# 03_MotorDriver.net
KiCad netlist of a schematic drawn in Altium Designer
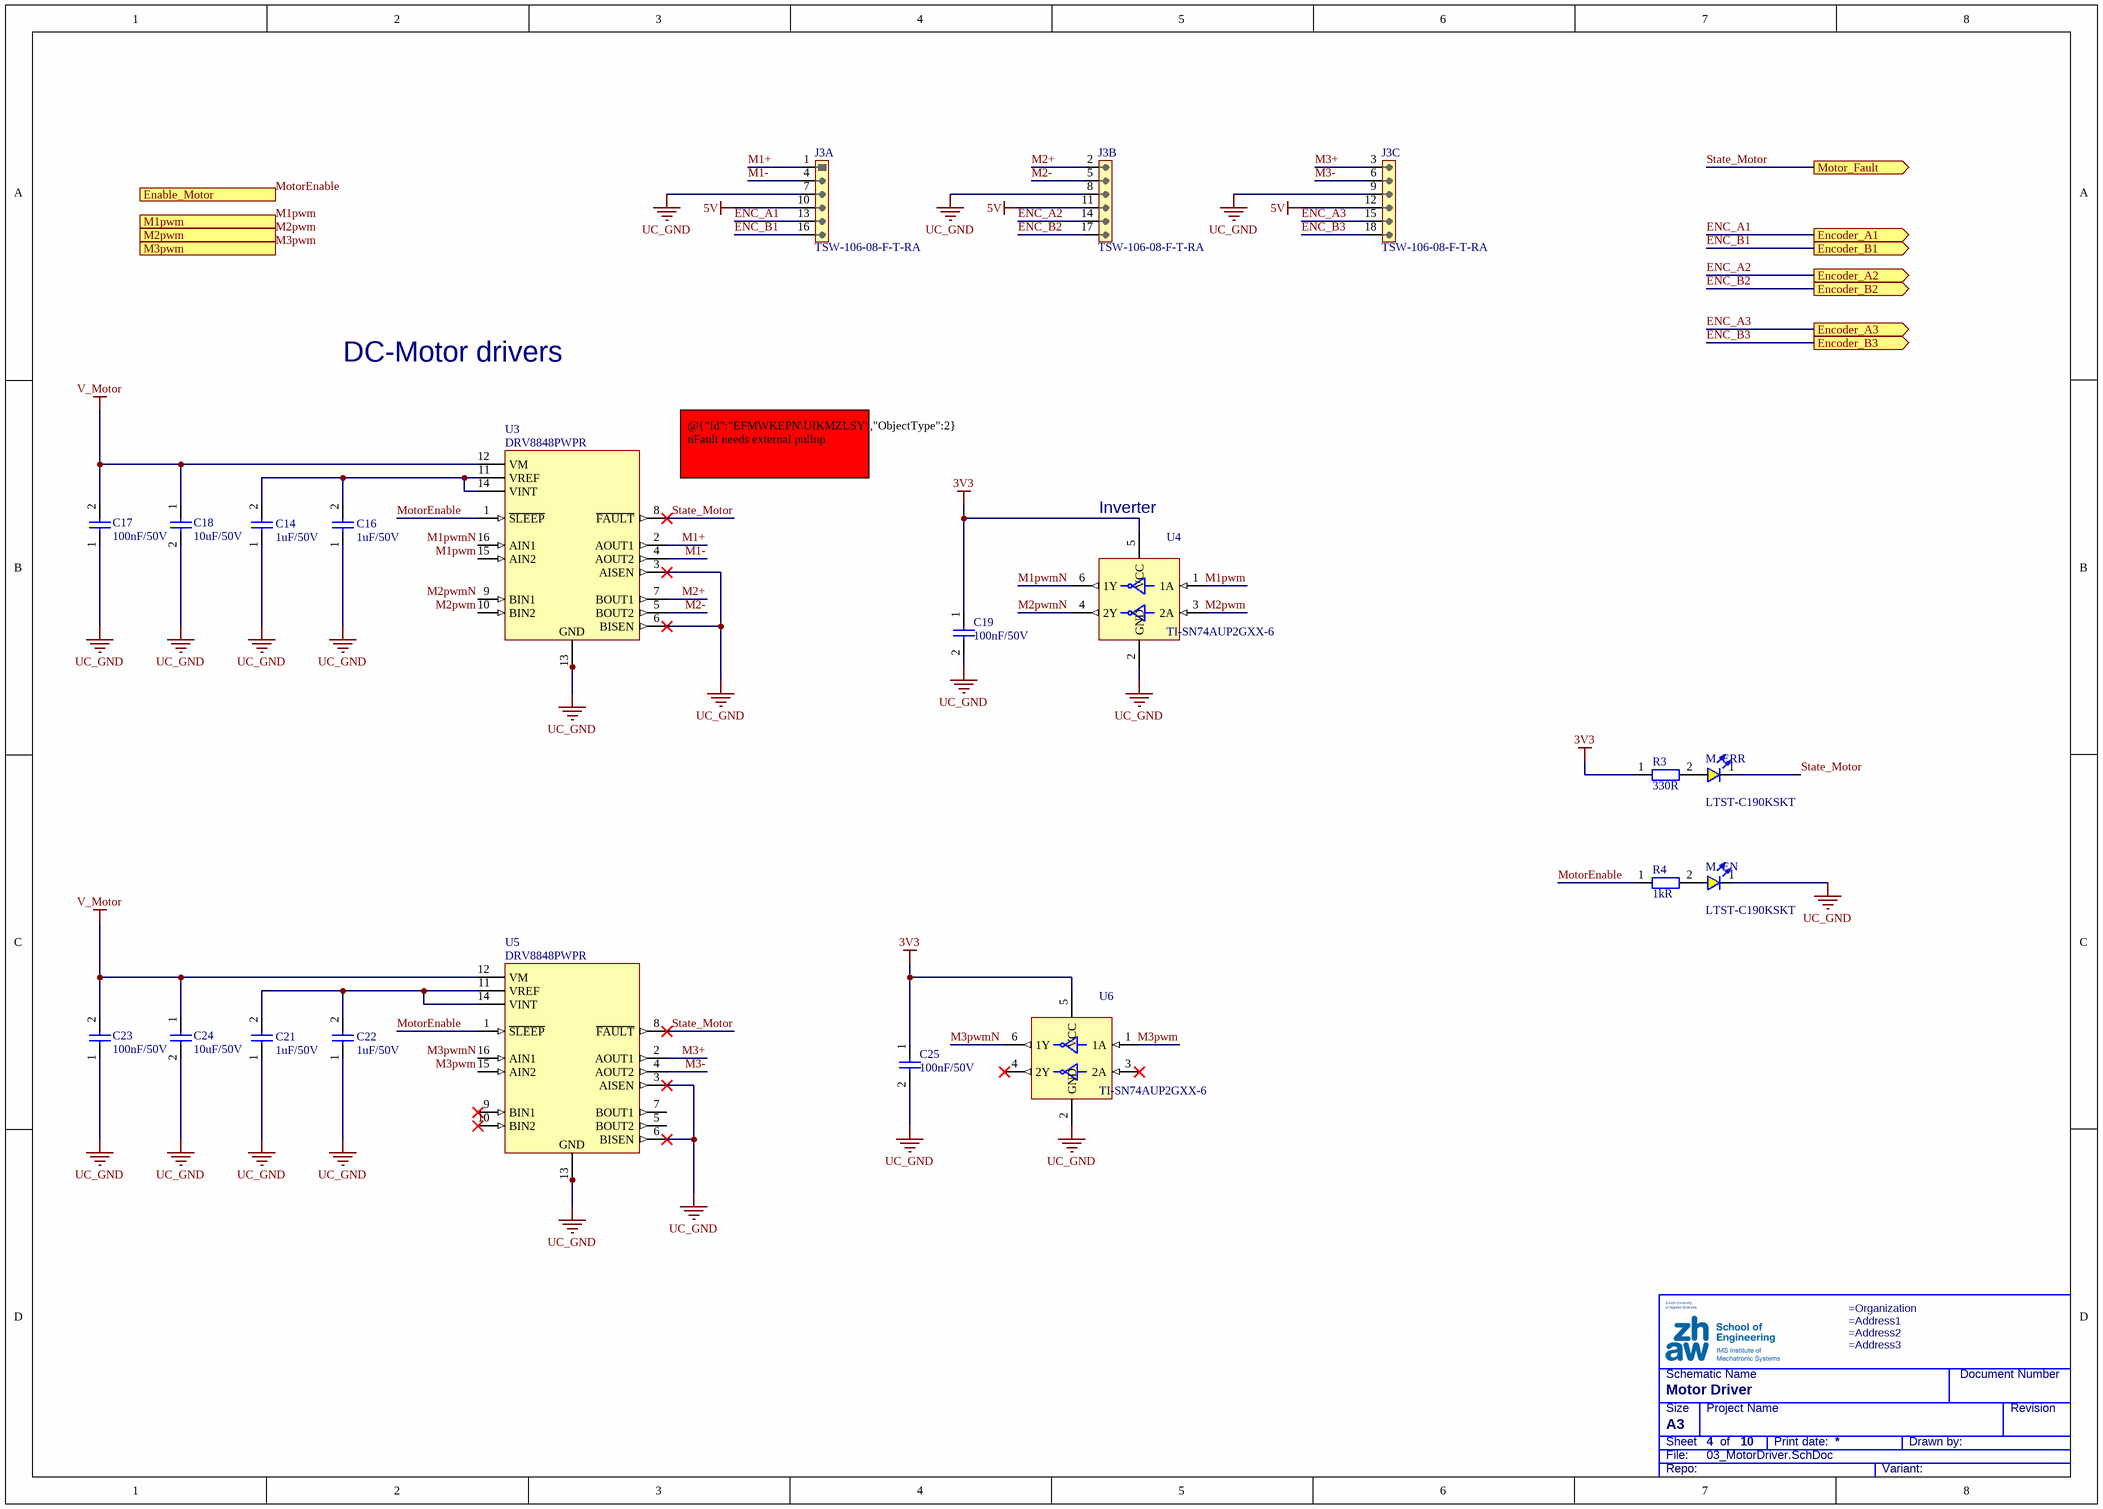
[diagram p0: 03_MotorDriver.SchDoc]

(export (version "E")
  (design (tool "Eeschema 10.0.6"))
  (components
    (comp (ref "C14")
      (value "1uF/50V")
      (footprint "CAPC1608X09L")
      (description "Cap MLCC, 1uF, 50V, X5R, 10%, 0603")
      (fields (field (name "TOLERANCE") "10%"))
      (libsource (lib "Altium Concord Pro on Altium 365") (part "CAP-NP-2"))
    )
    (comp (ref "C16")
      (value "1uF/50V")
      (footprint "CAPC1608X09L")
      (description "Cap MLCC, 1uF, 50V, X5R, 10%, 0603")
      (fields (field (name "TOLERANCE") "10%"))
      (libsource (lib "Altium Concord Pro on Altium 365") (part "CAP-NP-2"))
    )
    (comp (ref "C17")
      (value "100nF/50V")
      (footprint "CAPC1005X05L")
      (description "Cap MLCC, 100nF, 50V, X7R, 10%, 0402")
      (fields (field (name "TOLERANCE") "10%"))
      (libsource (lib "Altium Concord Pro on Altium 365") (part "CAP-NP-2"))
    )
    (comp (ref "C18")
      (value "10uF/50V")
      (footprint "CAPC3216X12L")
      (description "Cap MLCC, 10uF, 50V, X5R, 10%, 1206")
      (fields (field (name "TOLERANCE") "10%"))
      (libsource (lib "Altium Concord Pro on Altium 365") (part "CAP-NP-2"))
    )
    (comp (ref "C19")
      (value "100nF/50V")
      (footprint "CAPC1005X05L")
      (description "Cap MLCC, 100nF, 50V, X7R, 10%, 0402")
      (fields (field (name "TOLERANCE") "10%"))
      (libsource (lib "Altium Concord Pro on Altium 365") (part "CAP-NP-2"))
    )
    (comp (ref "C21")
      (value "1uF/50V")
      (footprint "CAPC1608X09L")
      (description "Cap MLCC, 1uF, 50V, X5R, 10%, 0603")
      (fields (field (name "TOLERANCE") "10%"))
      (libsource (lib "Altium Concord Pro on Altium 365") (part "CAP-NP-2"))
    )
    (comp (ref "C22")
      (value "1uF/50V")
      (footprint "CAPC1608X09L")
      (description "Cap MLCC, 1uF, 50V, X5R, 10%, 0603")
      (fields (field (name "TOLERANCE") "10%"))
      (libsource (lib "Altium Concord Pro on Altium 365") (part "CAP-NP-2"))
    )
    (comp (ref "C23")
      (value "100nF/50V")
      (footprint "CAPC1005X05L")
      (description "Cap MLCC, 100nF, 50V, X7R, 10%, 0402")
      (fields (field (name "TOLERANCE") "10%"))
      (libsource (lib "Altium Concord Pro on Altium 365") (part "CAP-NP-2"))
    )
    (comp (ref "C24")
      (value "10uF/50V")
      (footprint "CAPC3216X12L")
      (description "Cap MLCC, 10uF, 50V, X5R, 10%, 1206")
      (fields (field (name "TOLERANCE") "10%"))
      (libsource (lib "Altium Concord Pro on Altium 365") (part "CAP-NP-2"))
    )
    (comp (ref "C25")
      (value "100nF/50V")
      (footprint "CAPC1005X05L")
      (description "Cap MLCC, 100nF, 50V, X7R, 10%, 0402")
      (fields (field (name "TOLERANCE") "10%"))
      (libsource (lib "Altium Concord Pro on Altium 365") (part "CAP-NP-2"))
    )
    (comp (ref "J3")
      (value "TSW-106-08-F-T-RA")
      (footprint "SAMTEC_TSW-106-08-F-T-RA")
      (description "Header, 3x6Pin, Pitch 2.54mm, Male, Horizontal, THT")
      (fields (field (name "MANUFACTURER") "Samtec"))
      (libsource (lib "Altium Concord Pro on Altium 365") (part "Header 3x06 m"))
    )
    (comp (ref "M. EN")
      (value "LTST-C190KSKT")
      (footprint "LEDSC160X80X80-2Lye")
      (description "LED, Yellow, 20mA, 2.0V, 0603")
      (libsource (lib "Altium Concord Pro on Altium 365") (part "LED-YELLOW-AK-2"))
    )
    (comp (ref "M. ERR")
      (value "LTST-C190KSKT")
      (footprint "LEDSC160X80X80-2Lye")
      (description "LED, Yellow, 20mA, 2.0V, 0603")
      (libsource (lib "Altium Concord Pro on Altium 365") (part "LED-YELLOW-AK-2"))
    )
    (comp (ref "R3")
      (value "330R")
      (footprint "RESC1005X04L")
      (description "Res, 330R, 1%, 0.063W, 0402")
      (fields (field (name "POWER") "63mW") (field (name "TOLERANCE") "1%"))
      (libsource (lib "Altium Concord Pro on Altium 365") (part "RES-2"))
    )
    (comp (ref "R4")
      (value "1kR")
      (footprint "RESC1005X04L")
      (description "Res, 1kR, 1%, 0.1W, 0402")
      (fields (field (name "POWER") "100mW") (field (name "TOLERANCE") "1%"))
      (libsource (lib "Altium Concord Pro on Altium 365") (part "RES-2"))
    )
    (comp (ref "U3")
      (value "DRV8848PWPR")
      (footprint "TSOP65P640X120-17T277X246L")
      (description "Half Bridge, 4 Ch, 4..18V, Power 4..18V, 1A, 4Ap, TSOP-16, L5.1B6.2H1.2")
      (libsource (lib "Altium Concord Pro on Altium 365") (part "DRV8848"))
    )
    (comp (ref "U4")
      (value "TI-SN74AUP2GXX-6")
      (footprint "SOT65P210X110-6L")
      (description "INV, 2 Ch, 1 In/Ch, 0.8..5.5V, SC70-6, L2B2.2H1")
      (libsource (lib "Altium Concord Pro on Altium 365") (part "TI-SN74AUP2GXX-6"))
    )
    (comp (ref "U5")
      (value "DRV8848PWPR")
      (footprint "TSOP65P640X120-17T277X246L")
      (description "Half Bridge, 4 Ch, 4..18V, Power 4..18V, 1A, 4Ap, TSOP-16, L5.1B6.2H1.2")
      (libsource (lib "Altium Concord Pro on Altium 365") (part "DRV8848"))
    )
    (comp (ref "U6")
      (value "TI-SN74AUP2GXX-6")
      (footprint "SOT65P210X110-6L")
      (description "INV, 2 Ch, 1 In/Ch, 0.8..5.5V, SC70-6, L2B2.2H1")
      (libsource (lib "Altium Concord Pro on Altium 365") (part "TI-SN74AUP2GXX-6"))
    )
  )
  (nets
    (net (code "1") (name "/ENC_A1") (class "Default")
      (node (ref "J3") (pin "13") (pinfunction "13_13") (pintype "passive"))
    )
    (net (code "2") (name "/ENC_A2") (class "Default")
      (node (ref "J3") (pin "14") (pinfunction "14_14") (pintype "passive"))
    )
    (net (code "3") (name "/ENC_A3") (class "Default")
      (node (ref "J3") (pin "15") (pinfunction "15_15") (pintype "passive"))
    )
    (net (code "4") (name "/ENC_B1") (class "Default")
      (node (ref "J3") (pin "16") (pinfunction "16_16") (pintype "passive"))
    )
    (net (code "5") (name "/ENC_B2") (class "Default")
      (node (ref "J3") (pin "17") (pinfunction "17_17") (pintype "passive"))
    )
    (net (code "6") (name "/ENC_B3") (class "Default")
      (node (ref "J3") (pin "18") (pinfunction "18_18") (pintype "passive"))
    )
    (net (code "7") (name "/M1+") (class "Default")
      (node (ref "J3") (pin "1") (pinfunction "1_1") (pintype "passive"))
      (node (ref "U3") (pin "2") (pinfunction "AOUT1_2") (pintype "output"))
    )
    (net (code "8") (name "/M1-") (class "Default")
      (node (ref "J3") (pin "4") (pinfunction "4_4") (pintype "passive"))
      (node (ref "U3") (pin "4") (pinfunction "AOUT2_4") (pintype "output"))
    )
    (net (code "9") (name "/M1pwm") (class "Default")
      (node (ref "U3") (pin "15") (pinfunction "AIN2_15") (pintype "input"))
      (node (ref "U4") (pin "1") (pinfunction "1A_1") (pintype "input"))
    )
    (net (code "10") (name "/M1pwmN") (class "Default")
      (node (ref "U3") (pin "16") (pinfunction "AIN1_16") (pintype "input"))
      (node (ref "U4") (pin "6") (pinfunction "1Y_6") (pintype "output"))
    )
    (net (code "11") (name "/M2+") (class "Default")
      (node (ref "J3") (pin "2") (pinfunction "2_2") (pintype "passive"))
      (node (ref "U3") (pin "7") (pinfunction "BOUT1_7") (pintype "output"))
    )
    (net (code "12") (name "/M2-") (class "Default")
      (node (ref "J3") (pin "5") (pinfunction "5_5") (pintype "passive"))
      (node (ref "U3") (pin "5") (pinfunction "BOUT2_5") (pintype "output"))
    )
    (net (code "13") (name "/M2pwm") (class "Default")
      (node (ref "U3") (pin "10") (pinfunction "BIN2_10") (pintype "input"))
      (node (ref "U4") (pin "3") (pinfunction "2A_3") (pintype "input"))
    )
    (net (code "14") (name "/M2pwmN") (class "Default")
      (node (ref "U3") (pin "9") (pinfunction "BIN1_9") (pintype "input"))
      (node (ref "U4") (pin "4") (pinfunction "2Y_4") (pintype "output"))
    )
    (net (code "15") (name "/M3+") (class "Default")
      (node (ref "J3") (pin "3") (pinfunction "3_3") (pintype "passive"))
      (node (ref "U5") (pin "2") (pinfunction "AOUT1_2") (pintype "output"))
    )
    (net (code "16") (name "/M3-") (class "Default")
      (node (ref "J3") (pin "6") (pinfunction "6_6") (pintype "passive"))
      (node (ref "U5") (pin "4") (pinfunction "AOUT2_4") (pintype "output"))
    )
    (net (code "17") (name "/M3pwm") (class "Default")
      (node (ref "U5") (pin "15") (pinfunction "AIN2_15") (pintype "input"))
      (node (ref "U6") (pin "1") (pinfunction "1A_1") (pintype "input"))
    )
    (net (code "18") (name "/M3pwmN") (class "Default")
      (node (ref "U5") (pin "16") (pinfunction "AIN1_16") (pintype "input"))
      (node (ref "U6") (pin "6") (pinfunction "1Y_6") (pintype "output"))
    )
    (net (code "19") (name "/MotorEnable") (class "Default")
      (node (ref "R4") (pin "1") (pinfunction "1_1") (pintype "passive"))
      (node (ref "U3") (pin "1") (pinfunction "~{SLEEP}_1") (pintype "input"))
      (node (ref "U5") (pin "1") (pinfunction "~{SLEEP}_1") (pintype "input"))
    )
    (net (code "20") (name "/State_Motor") (class "Default")
      (node (ref "M. ERR") (pin "1") (pinfunction "K_1") (pintype "passive"))
      (node (ref "U3") (pin "8") (pinfunction "~{FAULT}_8") (pintype "output"))
      (node (ref "U5") (pin "8") (pinfunction "~{FAULT}_8") (pintype "output"))
    )
    (net (code "21") (name "3V3") (class "Default")
      (node (ref "C19") (pin "1") (pinfunction "1_1") (pintype "passive"))
      (node (ref "C25") (pin "1") (pinfunction "1_1") (pintype "passive"))
      (node (ref "R3") (pin "1") (pinfunction "1_1") (pintype "passive"))
      (node (ref "U4") (pin "5") (pinfunction "VCC_5") (pintype "power_in"))
      (node (ref "U6") (pin "5") (pinfunction "VCC_5") (pintype "power_in"))
    )
    (net (code "22") (name "5V") (class "Default")
      (node (ref "J3") (pin "10") (pinfunction "10_10") (pintype "passive"))
      (node (ref "J3") (pin "11") (pinfunction "11_11") (pintype "passive"))
      (node (ref "J3") (pin "12") (pinfunction "12_12") (pintype "passive"))
    )
    (net (code "23") (name "Net-(M. EN-A)") (class "Default")
      (node (ref "M. EN") (pin "2") (pinfunction "A_2") (pintype "passive"))
      (node (ref "R4") (pin "2") (pinfunction "2_2") (pintype "passive"))
    )
    (net (code "24") (name "Net-(M. ERR-A)") (class "Default")
      (node (ref "M. ERR") (pin "2") (pinfunction "A_2") (pintype "passive"))
      (node (ref "R3") (pin "2") (pinfunction "2_2") (pintype "passive"))
    )
    (net (code "25") (name "Net-(U3-VINT)") (class "Default")
      (node (ref "C14") (pin "2") (pinfunction "2_2") (pintype "passive"))
      (node (ref "C16") (pin "2") (pinfunction "2_2") (pintype "passive"))
      (node (ref "U3") (pin "11") (pinfunction "VREF_11") (pintype "power_in"))
      (node (ref "U3") (pin "14") (pinfunction "VINT_14") (pintype "power_in"))
    )
    (net (code "26") (name "Net-(U5-VINT)") (class "Default")
      (node (ref "C21") (pin "2") (pinfunction "2_2") (pintype "passive"))
      (node (ref "C22") (pin "2") (pinfunction "2_2") (pintype "passive"))
      (node (ref "U5") (pin "11") (pinfunction "VREF_11") (pintype "power_in"))
      (node (ref "U5") (pin "14") (pinfunction "VINT_14") (pintype "power_in"))
    )
    (net (code "27") (name "UC_GND") (class "Default")
      (node (ref "C14") (pin "1") (pinfunction "1_1") (pintype "passive"))
      (node (ref "C16") (pin "1") (pinfunction "1_1") (pintype "passive"))
      (node (ref "C17") (pin "1") (pinfunction "1_1") (pintype "passive"))
      (node (ref "C18") (pin "2") (pinfunction "2_2") (pintype "passive"))
      (node (ref "C19") (pin "2") (pinfunction "2_2") (pintype "passive"))
      (node (ref "C21") (pin "1") (pinfunction "1_1") (pintype "passive"))
      (node (ref "C22") (pin "1") (pinfunction "1_1") (pintype "passive"))
      (node (ref "C23") (pin "1") (pinfunction "1_1") (pintype "passive"))
      (node (ref "C24") (pin "2") (pinfunction "2_2") (pintype "passive"))
      (node (ref "C25") (pin "2") (pinfunction "2_2") (pintype "passive"))
      (node (ref "J3") (pin "7") (pinfunction "3_7") (pintype "passive"))
      (node (ref "J3") (pin "8") (pinfunction "8_8") (pintype "passive"))
      (node (ref "J3") (pin "9") (pinfunction "9_9") (pintype "passive"))
      (node (ref "M. EN") (pin "1") (pinfunction "K_1") (pintype "passive"))
      (node (ref "U3") (pin "13") (pinfunction "GND_13") (pintype "power_in"))
      (node (ref "U3") (pin "17") (pinfunction "GND_17") (pintype "power_in"))
      (node (ref "U3") (pin "3") (pinfunction "AISEN_3") (pintype "output"))
      (node (ref "U3") (pin "6") (pinfunction "BISEN_6") (pintype "output"))
      (node (ref "U4") (pin "2") (pinfunction "GND_2") (pintype "power_in"))
      (node (ref "U5") (pin "13") (pinfunction "GND_13") (pintype "power_in"))
      (node (ref "U5") (pin "17") (pinfunction "GND_17") (pintype "power_in"))
      (node (ref "U5") (pin "3") (pinfunction "AISEN_3") (pintype "output"))
      (node (ref "U5") (pin "6") (pinfunction "BISEN_6") (pintype "output"))
      (node (ref "U6") (pin "2") (pinfunction "GND_2") (pintype "power_in"))
    )
    (net (code "28") (name "V_Motor") (class "Default")
      (node (ref "C17") (pin "2") (pinfunction "2_2") (pintype "passive"))
      (node (ref "C18") (pin "1") (pinfunction "1_1") (pintype "passive"))
      (node (ref "C23") (pin "2") (pinfunction "2_2") (pintype "passive"))
      (node (ref "C24") (pin "1") (pinfunction "1_1") (pintype "passive"))
      (node (ref "U3") (pin "12") (pinfunction "VM_12") (pintype "power_in"))
      (node (ref "U5") (pin "12") (pinfunction "VM_12") (pintype "power_in"))
    )
    (net (code "29") (name "unconnected-(U5-BIN1-Pad9)") (class "Default")
      (node (ref "U5") (pin "9") (pinfunction "BIN1_9") (pintype "input+no_connect"))
    )
    (net (code "30") (name "unconnected-(U5-BIN2-Pad10)") (class "Default")
      (node (ref "U5") (pin "10") (pinfunction "BIN2_10") (pintype "input+no_connect"))
    )
    (net (code "31") (name "unconnected-(U5-BOUT1-Pad7)") (class "Default")
      (node (ref "U5") (pin "7") (pinfunction "BOUT1_7") (pintype "output"))
    )
    (net (code "32") (name "unconnected-(U5-BOUT2-Pad5)") (class "Default")
      (node (ref "U5") (pin "5") (pinfunction "BOUT2_5") (pintype "output"))
    )
    (net (code "33") (name "unconnected-(U6-2A-Pad3)") (class "Default")
      (node (ref "U6") (pin "3") (pinfunction "2A_3") (pintype "input+no_connect"))
    )
    (net (code "34") (name "unconnected-(U6-2Y-Pad4)") (class "Default")
      (node (ref "U6") (pin "4") (pinfunction "2Y_4") (pintype "output+no_connect"))
    )
  )
)
